# D1MSHO.net
KiCad netlist of a schematic drawn in EAGLE
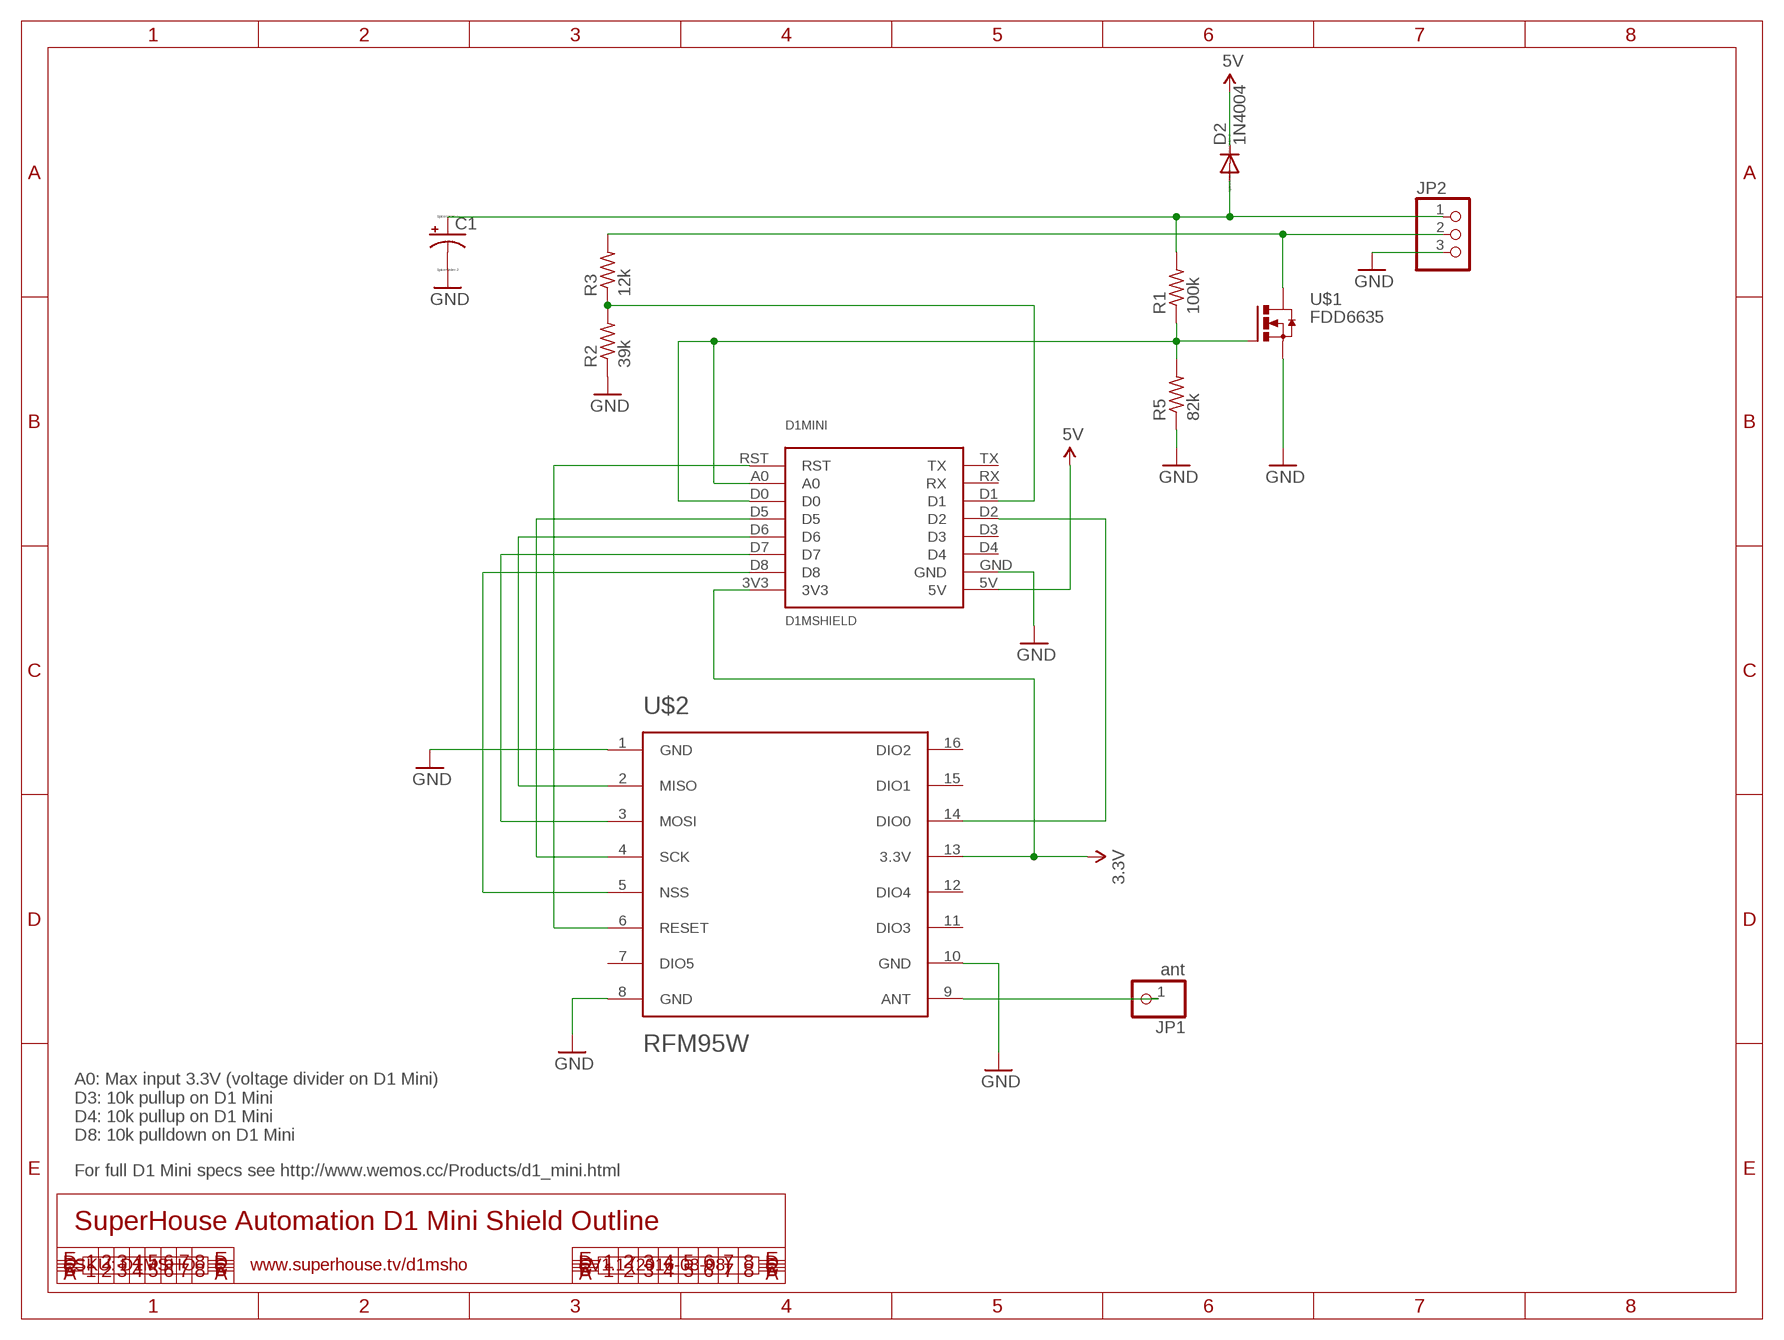
[diagram p0: schematic, sheet 1]

(export (version "E")
  (design (tool "Eeschema 10.0.6"))
  (components
    (comp (ref "C1")
      (value "CPOL-USE3.5-8")
      (footprint "eagle-import:E3,5-8")
      (libsource (lib "eagle-import") (part "CPOL-USE3.5-8"))
    )
    (comp (ref "D1MINI")
      (value "D1MSHIELD")
      (footprint "eagle-import:D1MSHELD")
      (libsource (lib "eagle-import") (part "D1MSHIELD"))
    )
    (comp (ref "D2")
      (value "1N4004")
      (footprint "eagle-import:DO41-10")
      (libsource (lib "eagle-import") (part "1N4004"))
    )
    (comp (ref "JP1")
      (value "ant")
      (footprint "eagle-import:1X01")
      (libsource (lib "eagle-import") (part "PINHD-1X1"))
    )
    (comp (ref "JP2")
      (value "PINHD-1X3/90")
      (footprint "eagle-import:1X03_90")
      (libsource (lib "eagle-import") (part "PINHD-1X3/90"))
    )
    (comp (ref "R1")
      (value "100k")
      (footprint "eagle-import:M0805")
      (libsource (lib "eagle-import") (part "R-US_M0805"))
    )
    (comp (ref "R2")
      (value "39k")
      (footprint "eagle-import:M0805")
      (libsource (lib "eagle-import") (part "R-US_M0805"))
    )
    (comp (ref "R3")
      (value "12k")
      (footprint "eagle-import:M0805")
      (libsource (lib "eagle-import") (part "R-US_M0805"))
    )
    (comp (ref "R5")
      (value "82k")
      (footprint "eagle-import:M0805")
      (libsource (lib "eagle-import") (part "R-US_M0805"))
    )
    (comp (ref "U$1")
      (value "FDD6635")
      (footprint "eagle-import:TO252")
      (libsource (lib "eagle-import") (part "FDD6635"))
    )
    (comp (ref "U$2")
      (value "RFM95W")
      (footprint "eagle-import:RFM")
      (libsource (lib "eagle-import") (part "RFM95W"))
    )
  )
  (nets
    (net (code "1") (name "3.3V") (class "Default")
      (node (ref "D1MINI") (pin "3V3") (pinfunction "3V3_3V3") (pintype "bidirectional"))
      (node (ref "U$2") (pin "13") (pinfunction "3.3V_13") (pintype "bidirectional"))
    )
    (net (code "2") (name "5V") (class "Default")
      (node (ref "D1MINI") (pin "5V") (pinfunction "5V_5V") (pintype "bidirectional"))
      (node (ref "D2") (pin "C") (pinfunction "C_C") (pintype "passive"))
    )
    (net (code "3") (name "GND") (class "Default")
      (node (ref "C1") (pin "-") (pinfunction "-_-") (pintype "passive"))
      (node (ref "D1MINI") (pin "GND") (pinfunction "GND_GND") (pintype "bidirectional"))
      (node (ref "JP2") (pin "3") (pinfunction "3_3") (pintype "passive"))
      (node (ref "R2") (pin "1") (pinfunction "1_1") (pintype "passive"))
      (node (ref "R5") (pin "1") (pinfunction "1_1") (pintype "passive"))
      (node (ref "U$1") (pin "2") (pinfunction "S_2") (pintype "passive"))
      (node (ref "U$2") (pin "1") (pinfunction "GND_1") (pintype "bidirectional"))
      (node (ref "U$2") (pin "10") (pinfunction "GND_10") (pintype "bidirectional"))
      (node (ref "U$2") (pin "8") (pinfunction "GND_8") (pintype "bidirectional"))
    )
    (net (code "4") (name "Net-(C1-Pad+)") (class "Default")
      (node (ref "C1") (pin "+") (pinfunction "+_+") (pintype "passive"))
      (node (ref "D2") (pin "A") (pinfunction "A_A") (pintype "passive"))
      (node (ref "JP2") (pin "1") (pinfunction "1_1") (pintype "passive"))
      (node (ref "R1") (pin "2") (pinfunction "2_2") (pintype "passive"))
    )
    (net (code "5") (name "Net-(D1MINI-PadD1)") (class "Default")
      (node (ref "D1MINI") (pin "D1") (pinfunction "D1_D1") (pintype "bidirectional"))
      (node (ref "R2") (pin "2") (pinfunction "2_2") (pintype "passive"))
      (node (ref "R3") (pin "1") (pinfunction "1_1") (pintype "passive"))
    )
    (net (code "6") (name "Net-(U$1-D)") (class "Default")
      (node (ref "JP2") (pin "2") (pinfunction "2_2") (pintype "passive"))
      (node (ref "R3") (pin "2") (pinfunction "2_2") (pintype "passive"))
      (node (ref "U$1") (pin "3") (pinfunction "D_3") (pintype "passive"))
    )
    (net (code "7") (name "Net-(U$1-G)") (class "Default")
      (node (ref "D1MINI") (pin "A0") (pinfunction "A0_A0") (pintype "bidirectional"))
      (node (ref "D1MINI") (pin "D0") (pinfunction "D0_D0") (pintype "bidirectional"))
      (node (ref "R1") (pin "1") (pinfunction "1_1") (pintype "passive"))
      (node (ref "R5") (pin "2") (pinfunction "2_2") (pintype "passive"))
      (node (ref "U$1") (pin "1") (pinfunction "G_1") (pintype "passive"))
    )
    (net (code "8") (name "Net-(U$2-ANT)") (class "Default")
      (node (ref "JP1") (pin "1") (pinfunction "1_1") (pintype "passive"))
      (node (ref "U$2") (pin "9") (pinfunction "ANT_9") (pintype "bidirectional"))
    )
    (net (code "9") (name "Net-(U$2-DIO0)") (class "Default")
      (node (ref "D1MINI") (pin "D2") (pinfunction "D2_D2") (pintype "bidirectional"))
      (node (ref "U$2") (pin "14") (pinfunction "DIO0_14") (pintype "bidirectional"))
    )
    (net (code "10") (name "Net-(U$2-MISO)") (class "Default")
      (node (ref "D1MINI") (pin "D6") (pinfunction "D6_D6") (pintype "bidirectional"))
      (node (ref "U$2") (pin "2") (pinfunction "MISO_2") (pintype "bidirectional"))
    )
    (net (code "11") (name "Net-(U$2-MOSI)") (class "Default")
      (node (ref "D1MINI") (pin "D7") (pinfunction "D7_D7") (pintype "bidirectional"))
      (node (ref "U$2") (pin "3") (pinfunction "MOSI_3") (pintype "bidirectional"))
    )
    (net (code "12") (name "Net-(U$2-NSS)") (class "Default")
      (node (ref "D1MINI") (pin "D8") (pinfunction "D8_D8") (pintype "bidirectional"))
      (node (ref "U$2") (pin "5") (pinfunction "NSS_5") (pintype "bidirectional"))
    )
    (net (code "13") (name "Net-(U$2-RESET)") (class "Default")
      (node (ref "D1MINI") (pin "RST") (pinfunction "RST_RST") (pintype "bidirectional"))
      (node (ref "U$2") (pin "6") (pinfunction "RESET_6") (pintype "bidirectional"))
    )
    (net (code "14") (name "Net-(U$2-SCK)") (class "Default")
      (node (ref "D1MINI") (pin "D5") (pinfunction "D5_D5") (pintype "bidirectional"))
      (node (ref "U$2") (pin "4") (pinfunction "SCK_4") (pintype "bidirectional"))
    )
    (net (code "15") (name "unconnected-(D1MINI-PadD3)") (class "Default")
      (node (ref "D1MINI") (pin "D3") (pinfunction "D3_D3") (pintype "bidirectional"))
    )
    (net (code "16") (name "unconnected-(D1MINI-PadD4)") (class "Default")
      (node (ref "D1MINI") (pin "D4") (pinfunction "D4_D4") (pintype "bidirectional"))
    )
    (net (code "17") (name "unconnected-(D1MINI-PadRX)") (class "Default")
      (node (ref "D1MINI") (pin "RX") (pinfunction "RX_RX") (pintype "bidirectional"))
    )
    (net (code "18") (name "unconnected-(D1MINI-PadTX)") (class "Default")
      (node (ref "D1MINI") (pin "TX") (pinfunction "TX_TX") (pintype "bidirectional"))
    )
    (net (code "19") (name "unconnected-(U$2-DIO1-Pad15)") (class "Default")
      (node (ref "U$2") (pin "15") (pinfunction "DIO1_15") (pintype "bidirectional"))
    )
    (net (code "20") (name "unconnected-(U$2-DIO2-Pad16)") (class "Default")
      (node (ref "U$2") (pin "16") (pinfunction "DIO2_16") (pintype "bidirectional"))
    )
    (net (code "21") (name "unconnected-(U$2-DIO3-Pad11)") (class "Default")
      (node (ref "U$2") (pin "11") (pinfunction "DIO3_11") (pintype "bidirectional"))
    )
    (net (code "22") (name "unconnected-(U$2-DIO4-Pad12)") (class "Default")
      (node (ref "U$2") (pin "12") (pinfunction "DIO4_12") (pintype "bidirectional"))
    )
    (net (code "23") (name "unconnected-(U$2-DIO5-Pad7)") (class "Default")
      (node (ref "U$2") (pin "7") (pinfunction "DIO5_7") (pintype "bidirectional"))
    )
  )
)
